# Schematic.net
KiCad netlist of a schematic drawn in Altium Designer
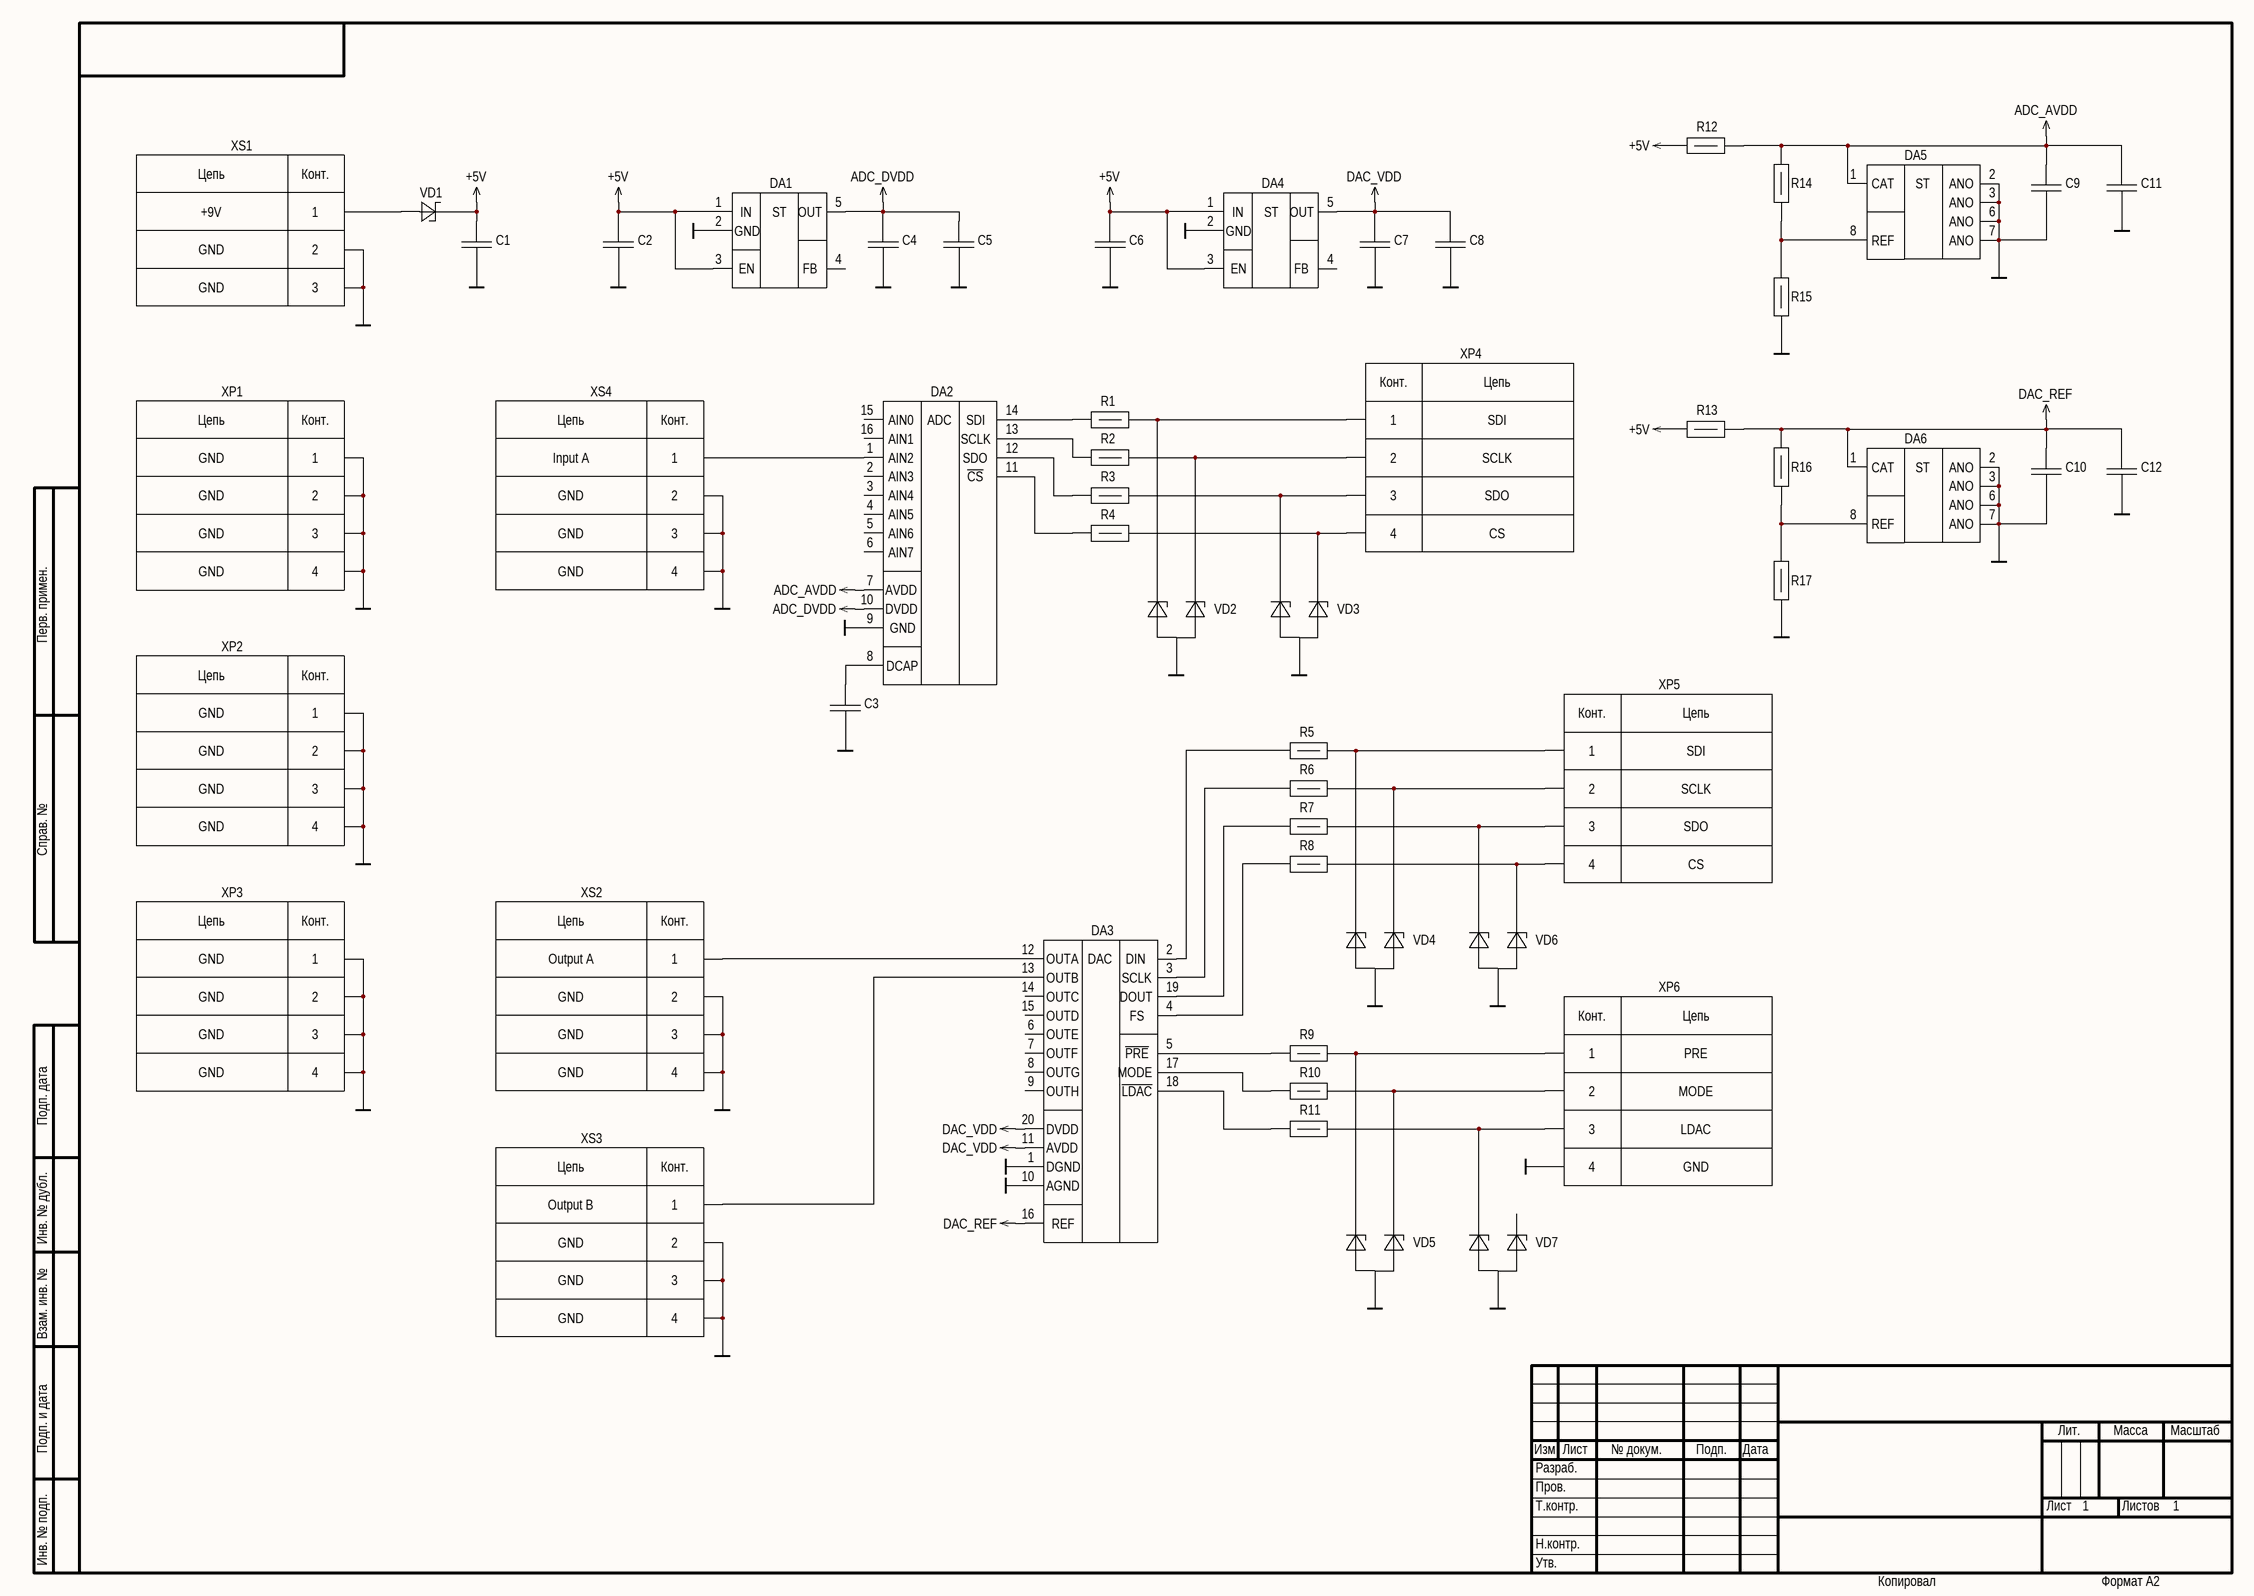
[diagram p0: Schematic.SchDoc]

(export (version "E")
  (design (tool "Eeschema 10.0.6"))
  (components
    (comp (ref "C1")
      (value "10 uF x 10 V")
      (footprint "CAPC2012X06N")
      (description "MLCC - Multilayer Ceramic Capacitors")
      (fields (field (name "TOLERANCE") "10%"))
      (libsource (lib "RLC") (part "KGM21AR71A106KU"))
    )
    (comp (ref "C2")
      (value "10 uF x 10 V")
      (footprint "CAPC2012X06N")
      (description "MLCC - Multilayer Ceramic Capacitors")
      (fields (field (name "TOLERANCE") "10%"))
      (libsource (lib "RLC") (part "KGM21AR71A106KU"))
    )
    (comp (ref "C3")
      (value "1 uF x 50 V")
      (footprint "CAPC2012X06N")
      (description "MLCC - Multilayer Ceramic Capacitors")
      (fields (field (name "TOLERANCE") "10%"))
      (libsource (lib "RLC") (part "KGF21KR71H105KU"))
    )
    (comp (ref "C4")
      (value "10 uF x 10 V")
      (footprint "CAPC2012X06N")
      (description "MLCC - Multilayer Ceramic Capacitors")
      (fields (field (name "TOLERANCE") "10%"))
      (libsource (lib "RLC") (part "KGM21AR71A106KU"))
    )
    (comp (ref "C5")
      (value "1 uF x 50 V")
      (footprint "CAPC2012X06N")
      (description "MLCC - Multilayer Ceramic Capacitors")
      (fields (field (name "TOLERANCE") "10%"))
      (libsource (lib "RLC") (part "KGF21KR71H105KU"))
    )
    (comp (ref "C6")
      (value "10 uF x 10 V")
      (footprint "CAPC2012X06N")
      (description "MLCC - Multilayer Ceramic Capacitors")
      (fields (field (name "TOLERANCE") "10%"))
      (libsource (lib "RLC") (part "KGM21AR71A106KU"))
    )
    (comp (ref "C7")
      (value "10 uF x 10 V")
      (footprint "CAPC2012X06N")
      (description "MLCC - Multilayer Ceramic Capacitors")
      (fields (field (name "TOLERANCE") "10%"))
      (libsource (lib "RLC") (part "KGM21AR71A106KU"))
    )
    (comp (ref "C8")
      (value "1 uF x 50 V")
      (footprint "CAPC2012X06N")
      (description "MLCC - Multilayer Ceramic Capacitors")
      (fields (field (name "TOLERANCE") "10%"))
      (libsource (lib "RLC") (part "KGF21KR71H105KU"))
    )
    (comp (ref "C9")
      (value "1 uF x 50 V")
      (footprint "CAPC2012X06N")
      (description "MLCC - Multilayer Ceramic Capacitors")
      (fields (field (name "TOLERANCE") "10%"))
      (libsource (lib "RLC") (part "KGF21KR71H105KU"))
    )
    (comp (ref "C10")
      (value "1 uF x 50 V")
      (footprint "CAPC2012X06N")
      (description "MLCC - Multilayer Ceramic Capacitors")
      (fields (field (name "TOLERANCE") "10%"))
      (libsource (lib "RLC") (part "KGF21KR71H105KU"))
    )
    (comp (ref "C11")
      (value "10 uF x 10 V")
      (footprint "CAPC2012X06N")
      (description "MLCC - Multilayer Ceramic Capacitors")
      (fields (field (name "TOLERANCE") "10%"))
      (libsource (lib "RLC") (part "KGM21AR71A106KU"))
    )
    (comp (ref "C12")
      (value "10 uF x 10 V")
      (footprint "CAPC2012X06N")
      (description "MLCC - Multilayer Ceramic Capacitors")
      (fields (field (name "TOLERANCE") "10%"))
      (libsource (lib "RLC") (part "KGM21AR71A106KU"))
    )
    (comp (ref "DA1")
      (value "TPS76333DBVT")
      (footprint "DBV0005A")
      (description "150mA, 10V, Low-Dropout Voltage Regulator")
      (libsource (lib "TPS763") (part "TPS76333DBVT"))
    )
    (comp (ref "DA2")
      (value "ADS7038IRTET")
      (footprint "RTE0016C")
      (description "Small, 8-Channel, 12-Bit ADC With SPI Interface, GPIOs, and CRC")
      (libsource (lib "ADS7038x") (part "ADS7038IRTET"))
    )
    (comp (ref "DA3")
      (value "TLV5631IPW")
      (footprint "PW0020A")
      (libsource (lib "TLV563x") (part "TLV5631IPW"))
    )
    (comp (ref "DA4")
      (value "TPS76333DBVT")
      (footprint "DBV0005A")
      (description "150mA, 10V, Low-Dropout Voltage Regulator")
      (libsource (lib "TPS763") (part "TPS76333DBVT"))
    )
    (comp (ref "DA5") (value "TL431AID") (footprint "D0008A") (libsource (lib "TL431") (part "TL431AID")))
    (comp (ref "DA6") (value "TL431AID") (footprint "D0008A") (libsource (lib "TL431") (part "TL431AID")))
    (comp (ref "R1")
      (value "22 Ohms")
      (footprint "RESC2012X06N")
      (description "Thick Film Chip Resistors")
      (fields (field (name "TOLERANCE") "1%"))
      (libsource (lib "RLC") (part "RCA080522R0FKEA"))
    )
    (comp (ref "R2")
      (value "22 Ohms")
      (footprint "RESC2012X06N")
      (description "Thick Film Chip Resistors")
      (fields (field (name "TOLERANCE") "1%"))
      (libsource (lib "RLC") (part "RCA080522R0FKEA"))
    )
    (comp (ref "R3")
      (value "22 Ohms")
      (footprint "RESC2012X06N")
      (description "Thick Film Chip Resistors")
      (fields (field (name "TOLERANCE") "1%"))
      (libsource (lib "RLC") (part "RCA080522R0FKEA"))
    )
    (comp (ref "R4")
      (value "22 Ohms")
      (footprint "RESC2012X06N")
      (description "Thick Film Chip Resistors")
      (fields (field (name "TOLERANCE") "1%"))
      (libsource (lib "RLC") (part "RCA080522R0FKEA"))
    )
    (comp (ref "R5")
      (value "22 Ohms")
      (footprint "RESC2012X06N")
      (description "Thick Film Chip Resistors")
      (fields (field (name "TOLERANCE") "1%"))
      (libsource (lib "RLC") (part "RCA080522R0FKEA"))
    )
    (comp (ref "R6")
      (value "22 Ohms")
      (footprint "RESC2012X06N")
      (description "Thick Film Chip Resistors")
      (fields (field (name "TOLERANCE") "1%"))
      (libsource (lib "RLC") (part "RCA080522R0FKEA"))
    )
    (comp (ref "R7")
      (value "22 Ohms")
      (footprint "RESC2012X06N")
      (description "Thick Film Chip Resistors")
      (fields (field (name "TOLERANCE") "1%"))
      (libsource (lib "RLC") (part "RCA080522R0FKEA"))
    )
    (comp (ref "R8")
      (value "22 Ohms")
      (footprint "RESC2012X06N")
      (description "Thick Film Chip Resistors")
      (fields (field (name "TOLERANCE") "1%"))
      (libsource (lib "RLC") (part "RCA080522R0FKEA"))
    )
    (comp (ref "R9")
      (value "22 Ohms")
      (footprint "RESC2012X06N")
      (description "Thick Film Chip Resistors")
      (fields (field (name "TOLERANCE") "1%"))
      (libsource (lib "RLC") (part "RCA080522R0FKEA"))
    )
    (comp (ref "R10")
      (value "22 Ohms")
      (footprint "RESC2012X06N")
      (description "Thick Film Chip Resistors")
      (fields (field (name "TOLERANCE") "1%"))
      (libsource (lib "RLC") (part "RCA080522R0FKEA"))
    )
    (comp (ref "R11")
      (value "22 Ohms")
      (footprint "RESC2012X06N")
      (description "Thick Film Chip Resistors")
      (fields (field (name "TOLERANCE") "1%"))
      (libsource (lib "RLC") (part "RCA080522R0FKEA"))
    )
    (comp (ref "R12")
      (value "182 Ohms")
      (footprint "RESC2012X06N")
      (description "Thick Film Chip Resistors")
      (fields (field (name "TOLERANCE") "1%"))
      (libsource (lib "RLC") (part "CR0805-FX-1820ELF"))
    )
    (comp (ref "R13")
      (value "182 Ohms")
      (footprint "RESC2012X06N")
      (description "Thick Film Chip Resistors")
      (fields (field (name "TOLERANCE") "1%"))
      (libsource (lib "RLC") (part "CR0805-FX-1820ELF"))
    )
    (comp (ref "R14")
      (value "3.3 kOhms")
      (footprint "RESC2012X06N")
      (description "Thick Film Chip Resistors")
      (fields (field (name "TOLERANCE") "1%"))
      (libsource (lib "RLC") (part "CR0805-FX-3301ELF"))
    )
    (comp (ref "R15")
      (value "10 kOhms")
      (footprint "RESC2012X06N")
      (description "Thick Film Chip Resistors")
      (fields (field (name "TOLERANCE") "1%"))
      (libsource (lib "RLC") (part "ERJ-6ENF1002V"))
    )
    (comp (ref "R16")
      (value "3.3 kOhms")
      (footprint "RESC2012X06N")
      (description "Thick Film Chip Resistors")
      (fields (field (name "TOLERANCE") "1%"))
      (libsource (lib "RLC") (part "CR0805-FX-3301ELF"))
    )
    (comp (ref "R17")
      (value "10 kOhms")
      (footprint "RESC2012X06N")
      (description "Thick Film Chip Resistors")
      (fields (field (name "TOLERANCE") "1%"))
      (libsource (lib "RLC") (part "ERJ-6ENF1002V"))
    )
    (comp (ref "VD1")
      (value "BAT54W-HG3-18")
      (footprint "SOD-123")
      (description "Schottky Diodes & Rectifiers 30V Schottky DIODE")
      (libsource (lib "BAT54W-HG3-18") (part "BAT54W-HG3-18"))
    )
    (comp (ref "VD2")
      (value "SP0502BAHT")
      (footprint "SOT23")
      (description "TVS Diode Array")
      (libsource (lib "SP05xxBA") (part "SP0502BAHT"))
    )
    (comp (ref "VD3")
      (value "SP0502BAHT")
      (footprint "SOT23")
      (description "TVS Diode Array")
      (libsource (lib "SP05xxBA") (part "SP0502BAHT"))
    )
    (comp (ref "VD4")
      (value "SP0502BAHT")
      (footprint "SOT23")
      (description "TVS Diode Array")
      (libsource (lib "SP05xxBA") (part "SP0502BAHT"))
    )
    (comp (ref "VD5")
      (value "SP0502BAHT")
      (footprint "SOT23")
      (description "TVS Diode Array")
      (libsource (lib "SP05xxBA") (part "SP0502BAHT"))
    )
    (comp (ref "VD6")
      (value "SP0502BAHT")
      (footprint "SOT23")
      (description "TVS Diode Array")
      (libsource (lib "SP05xxBA") (part "SP0502BAHT"))
    )
    (comp (ref "VD7")
      (value "SP0502BAHT")
      (footprint "SOT23")
      (description "TVS Diode Array")
      (libsource (lib "SP05xxBA") (part "SP0502BAHT"))
    )
    (comp (ref "XP1")
      (value "M20-9770346-4")
      (footprint "HDRV4W64P254_1X4_1016X254X834P")
      (description "Header 2.54mm")
      (libsource (lib "") (part "M20-9770346-4_1"))
    )
    (comp (ref "XP2")
      (value "M20-9770346-4")
      (footprint "HDRV4W64P254_1X4_1016X254X834P")
      (description "Header 2.54mm")
      (libsource (lib "") (part "M20-9770346-4_1"))
    )
    (comp (ref "XP3")
      (value "M20-9770346-4")
      (footprint "HDRV4W64P254_1X4_1016X254X834P")
      (description "Header 2.54mm")
      (libsource (lib "") (part "M20-9770346-4_1"))
    )
    (comp (ref "XP4")
      (value "M20-9770346-4")
      (footprint "HDRV4W64P254_1X4_1016X254X834P")
      (description "Header 2.54mm")
      (libsource (lib "M20-9770346-4") (part "M20-9770346-4"))
    )
    (comp (ref "XP5")
      (value "M20-9770346-4")
      (footprint "HDRV4W64P254_1X4_1016X254X834P")
      (description "Header 2.54mm")
      (libsource (lib "M20-9770346-4") (part "M20-9770346-4"))
    )
    (comp (ref "XP6")
      (value "M20-9770346-4")
      (footprint "HDRV4W64P254_1X4_1016X254X834P")
      (description "Header 2.54mm")
      (libsource (lib "") (part "M20-9770346-4_2"))
    )
    (comp (ref "XS1")
      (value "PJ-002AH")
      (footprint "PJ-002AH (Same Sky)")
      (description "DC POWER JACK")
      (libsource (lib "PJ-002AH") (part "PJ-002AH"))
    )
    (comp (ref "XS2")
      (value "0731385003")
      (footprint "0731385003 (Molex)")
      (description "BNC Connector Jack")
      (libsource (lib "") (part "0731385003_2"))
    )
    (comp (ref "XS3")
      (value "0731385003")
      (footprint "0731385003 (Molex)")
      (description "BNC Connector Jack")
      (libsource (lib "0731385003") (part "0731385003"))
    )
    (comp (ref "XS4")
      (value "0731385003")
      (footprint "0731385003 (Molex)")
      (description "BNC Connector Jack")
      (libsource (lib "") (part "0731385003_1"))
    )
  )
  (nets
    (net (code "1") (name "+5V") (class "Default")
      (node (ref "C1") (pin "1") (pinfunction "1_1") (pintype "passive"))
      (node (ref "C2") (pin "1") (pinfunction "1_1") (pintype "passive"))
      (node (ref "C6") (pin "1") (pinfunction "1_1") (pintype "passive"))
      (node (ref "DA1") (pin "1") (pinfunction "IN_1") (pintype "passive"))
      (node (ref "DA1") (pin "3") (pinfunction "EN_3") (pintype "passive"))
      (node (ref "DA4") (pin "1") (pinfunction "IN_1") (pintype "passive"))
      (node (ref "DA4") (pin "3") (pinfunction "EN_3") (pintype "passive"))
      (node (ref "R12") (pin "1") (pinfunction "1_1") (pintype "passive"))
      (node (ref "R13") (pin "1") (pinfunction "1_1") (pintype "passive"))
      (node (ref "VD1") (pin "1") (pinfunction "1_1") (pintype "passive"))
    )
    (net (code "2") (name "ADC_AVDD") (class "Default")
      (node (ref "C11") (pin "1") (pinfunction "1_1") (pintype "passive"))
      (node (ref "C9") (pin "1") (pinfunction "1_1") (pintype "passive"))
      (node (ref "DA2") (pin "7") (pinfunction "AVDD_7") (pintype "passive"))
      (node (ref "DA5") (pin "1") (pinfunction "CAT_1") (pintype "passive"))
      (node (ref "R12") (pin "2") (pinfunction "2_2") (pintype "passive"))
      (node (ref "R14") (pin "2") (pinfunction "2_2") (pintype "passive"))
    )
    (net (code "3") (name "ADC_DVDD") (class "Default")
      (node (ref "C4") (pin "1") (pinfunction "1_1") (pintype "passive"))
      (node (ref "C5") (pin "1") (pinfunction "1_1") (pintype "passive"))
      (node (ref "DA1") (pin "5") (pinfunction "OUT_5") (pintype "passive"))
      (node (ref "DA2") (pin "10") (pinfunction "DVDD_10") (pintype "passive"))
    )
    (net (code "4") (name "DAC_REF") (class "Default")
      (node (ref "C10") (pin "1") (pinfunction "1_1") (pintype "passive"))
      (node (ref "C12") (pin "1") (pinfunction "1_1") (pintype "passive"))
      (node (ref "DA3") (pin "16") (pinfunction "REF_16") (pintype "passive"))
      (node (ref "DA6") (pin "1") (pinfunction "CAT_1") (pintype "passive"))
      (node (ref "R13") (pin "2") (pinfunction "2_2") (pintype "passive"))
      (node (ref "R16") (pin "2") (pinfunction "2_2") (pintype "passive"))
    )
    (net (code "5") (name "DAC_VDD") (class "Default")
      (node (ref "C7") (pin "1") (pinfunction "1_1") (pintype "passive"))
      (node (ref "C8") (pin "1") (pinfunction "1_1") (pintype "passive"))
      (node (ref "DA3") (pin "11") (pinfunction "AVDD_11") (pintype "passive"))
      (node (ref "DA3") (pin "20") (pinfunction "DVDD_20") (pintype "passive"))
      (node (ref "DA4") (pin "5") (pinfunction "OUT_5") (pintype "passive"))
    )
    (net (code "6") (name "GND") (class "Default")
      (node (ref "C1") (pin "2") (pinfunction "2_2") (pintype "passive"))
      (node (ref "C10") (pin "2") (pinfunction "2_2") (pintype "passive"))
      (node (ref "C11") (pin "2") (pinfunction "2_2") (pintype "passive"))
      (node (ref "C12") (pin "2") (pinfunction "2_2") (pintype "passive"))
      (node (ref "C2") (pin "2") (pinfunction "2_2") (pintype "passive"))
      (node (ref "C3") (pin "2") (pinfunction "2_2") (pintype "passive"))
      (node (ref "C4") (pin "2") (pinfunction "2_2") (pintype "passive"))
      (node (ref "C5") (pin "2") (pinfunction "2_2") (pintype "passive"))
      (node (ref "C6") (pin "2") (pinfunction "2_2") (pintype "passive"))
      (node (ref "C7") (pin "2") (pinfunction "2_2") (pintype "passive"))
      (node (ref "C8") (pin "2") (pinfunction "2_2") (pintype "passive"))
      (node (ref "C9") (pin "2") (pinfunction "2_2") (pintype "passive"))
      (node (ref "DA1") (pin "2") (pinfunction "GND_2") (pintype "passive"))
      (node (ref "DA2") (pin "9") (pinfunction "GND_9") (pintype "passive"))
      (node (ref "DA3") (pin "1") (pinfunction "DGND_1") (pintype "passive"))
      (node (ref "DA3") (pin "10") (pinfunction "AGND_10") (pintype "passive"))
      (node (ref "DA4") (pin "2") (pinfunction "GND_2") (pintype "passive"))
      (node (ref "DA5") (pin "2") (pinfunction "ANO_2") (pintype "passive"))
      (node (ref "DA5") (pin "3") (pinfunction "ANO_3") (pintype "passive"))
      (node (ref "DA5") (pin "6") (pinfunction "ANO_6") (pintype "passive"))
      (node (ref "DA5") (pin "7") (pinfunction "ANO_7") (pintype "passive"))
      (node (ref "DA6") (pin "2") (pinfunction "ANO_2") (pintype "passive"))
      (node (ref "DA6") (pin "3") (pinfunction "ANO_3") (pintype "passive"))
      (node (ref "DA6") (pin "6") (pinfunction "ANO_6") (pintype "passive"))
      (node (ref "DA6") (pin "7") (pinfunction "ANO_7") (pintype "passive"))
      (node (ref "R15") (pin "1") (pinfunction "1_1") (pintype "passive"))
      (node (ref "R17") (pin "1") (pinfunction "1_1") (pintype "passive"))
      (node (ref "VD2") (pin "3") (pinfunction "3_3") (pintype "passive"))
      (node (ref "VD3") (pin "3") (pinfunction "3_3") (pintype "passive"))
      (node (ref "VD4") (pin "3") (pinfunction "3_3") (pintype "passive"))
      (node (ref "VD5") (pin "3") (pinfunction "3_3") (pintype "passive"))
      (node (ref "VD6") (pin "3") (pinfunction "3_3") (pintype "passive"))
      (node (ref "VD7") (pin "3") (pinfunction "3_3") (pintype "passive"))
      (node (ref "XP1") (pin "1") (pinfunction "GND_1") (pintype "passive"))
      (node (ref "XP1") (pin "2") (pinfunction "GND_2") (pintype "passive"))
      (node (ref "XP1") (pin "3") (pinfunction "GND_3") (pintype "passive"))
      (node (ref "XP1") (pin "4") (pinfunction "GND_4") (pintype "passive"))
      (node (ref "XP2") (pin "1") (pinfunction "GND_1") (pintype "passive"))
      (node (ref "XP2") (pin "2") (pinfunction "GND_2") (pintype "passive"))
      (node (ref "XP2") (pin "3") (pinfunction "GND_3") (pintype "passive"))
      (node (ref "XP2") (pin "4") (pinfunction "GND_4") (pintype "passive"))
      (node (ref "XP3") (pin "1") (pinfunction "GND_1") (pintype "passive"))
      (node (ref "XP3") (pin "2") (pinfunction "GND_2") (pintype "passive"))
      (node (ref "XP3") (pin "3") (pinfunction "GND_3") (pintype "passive"))
      (node (ref "XP3") (pin "4") (pinfunction "GND_4") (pintype "passive"))
      (node (ref "XP6") (pin "4") (pinfunction "GND_4") (pintype "passive"))
      (node (ref "XS1") (pin "2") (pinfunction "GND_2") (pintype "passive"))
      (node (ref "XS1") (pin "3") (pinfunction "GND_3") (pintype "passive"))
      (node (ref "XS2") (pin "2") (pinfunction "GND_2") (pintype "passive"))
      (node (ref "XS2") (pin "3") (pinfunction "GND_3") (pintype "passive"))
      (node (ref "XS2") (pin "4") (pinfunction "GND_4") (pintype "passive"))
      (node (ref "XS3") (pin "2") (pinfunction "GND_2") (pintype "passive"))
      (node (ref "XS3") (pin "3") (pinfunction "GND_3") (pintype "passive"))
      (node (ref "XS3") (pin "4") (pinfunction "GND_4") (pintype "passive"))
      (node (ref "XS4") (pin "2") (pinfunction "GND_2") (pintype "passive"))
      (node (ref "XS4") (pin "3") (pinfunction "GND_3") (pintype "passive"))
      (node (ref "XS4") (pin "4") (pinfunction "GND_4") (pintype "passive"))
    )
    (net (code "7") (name "Net-(DA2-AIN2)") (class "Default")
      (node (ref "DA2") (pin "1") (pinfunction "AIN2_1") (pintype "passive"))
      (node (ref "XS4") (pin "1") (pinfunction "Input_A_1") (pintype "passive"))
    )
    (net (code "8") (name "Net-(DA2-CS)") (class "Default")
      (node (ref "DA2") (pin "11") (pinfunction "CS_11") (pintype "passive"))
      (node (ref "R4") (pin "1") (pinfunction "1_1") (pintype "passive"))
    )
    (net (code "9") (name "Net-(DA2-DCAP)") (class "Default")
      (node (ref "C3") (pin "1") (pinfunction "1_1") (pintype "passive"))
      (node (ref "DA2") (pin "8") (pinfunction "DCAP_8") (pintype "passive"))
    )
    (net (code "10") (name "Net-(DA2-SCLK)") (class "Default")
      (node (ref "DA2") (pin "13") (pinfunction "SCLK_13") (pintype "passive"))
      (node (ref "R2") (pin "1") (pinfunction "1_1") (pintype "passive"))
    )
    (net (code "11") (name "Net-(DA2-SDI)") (class "Default")
      (node (ref "DA2") (pin "14") (pinfunction "SDI_14") (pintype "passive"))
      (node (ref "R1") (pin "1") (pinfunction "1_1") (pintype "passive"))
    )
    (net (code "12") (name "Net-(DA2-SDO)") (class "Default")
      (node (ref "DA2") (pin "12") (pinfunction "SDO_12") (pintype "passive"))
      (node (ref "R3") (pin "1") (pinfunction "1_1") (pintype "passive"))
    )
    (net (code "13") (name "Net-(DA3-DIN)") (class "Default")
      (node (ref "DA3") (pin "2") (pinfunction "DIN_2") (pintype "passive"))
      (node (ref "R5") (pin "1") (pinfunction "1_1") (pintype "passive"))
    )
    (net (code "14") (name "Net-(DA3-DOUT)") (class "Default")
      (node (ref "DA3") (pin "19") (pinfunction "DOUT_19") (pintype "passive"))
      (node (ref "R7") (pin "1") (pinfunction "1_1") (pintype "passive"))
    )
    (net (code "15") (name "Net-(DA3-FS)") (class "Default")
      (node (ref "DA3") (pin "4") (pinfunction "FS_4") (pintype "passive"))
      (node (ref "R8") (pin "1") (pinfunction "1_1") (pintype "passive"))
    )
    (net (code "16") (name "Net-(DA3-LDAC)") (class "Default")
      (node (ref "DA3") (pin "18") (pinfunction "LDAC_18") (pintype "passive"))
      (node (ref "R11") (pin "1") (pinfunction "1_1") (pintype "passive"))
    )
    (net (code "17") (name "Net-(DA3-MODE)") (class "Default")
      (node (ref "DA3") (pin "17") (pinfunction "MODE_17") (pintype "passive"))
      (node (ref "R10") (pin "1") (pinfunction "1_1") (pintype "passive"))
    )
    (net (code "18") (name "Net-(DA3-OUTA)") (class "Default")
      (node (ref "DA3") (pin "12") (pinfunction "OUTA_12") (pintype "passive"))
      (node (ref "XS2") (pin "1") (pinfunction "Output_A_1") (pintype "passive"))
    )
    (net (code "19") (name "Net-(DA3-OUTB)") (class "Default")
      (node (ref "DA3") (pin "13") (pinfunction "OUTB_13") (pintype "passive"))
      (node (ref "XS3") (pin "1") (pinfunction "Output_B_1") (pintype "passive"))
    )
    (net (code "20") (name "Net-(DA3-PRE)") (class "Default")
      (node (ref "DA3") (pin "5") (pinfunction "PRE_5") (pintype "passive"))
      (node (ref "R9") (pin "1") (pinfunction "1_1") (pintype "passive"))
    )
    (net (code "21") (name "Net-(DA3-SCLK)") (class "Default")
      (node (ref "DA3") (pin "3") (pinfunction "SCLK_3") (pintype "passive"))
      (node (ref "R6") (pin "1") (pinfunction "1_1") (pintype "passive"))
    )
    (net (code "22") (name "Net-(DA5-REF)") (class "Default")
      (node (ref "DA5") (pin "8") (pinfunction "REF_8") (pintype "passive"))
      (node (ref "R14") (pin "1") (pinfunction "1_1") (pintype "passive"))
      (node (ref "R15") (pin "2") (pinfunction "2_2") (pintype "passive"))
    )
    (net (code "23") (name "Net-(DA6-REF)") (class "Default")
      (node (ref "DA6") (pin "8") (pinfunction "REF_8") (pintype "passive"))
      (node (ref "R16") (pin "1") (pinfunction "1_1") (pintype "passive"))
      (node (ref "R17") (pin "2") (pinfunction "2_2") (pintype "passive"))
    )
    (net (code "24") (name "Net-(XP4-CS)") (class "Default")
      (node (ref "R4") (pin "2") (pinfunction "2_2") (pintype "passive"))
      (node (ref "VD3") (pin "1") (pinfunction "1_1") (pintype "passive"))
      (node (ref "XP4") (pin "4") (pinfunction "CS_4") (pintype "passive"))
    )
    (net (code "25") (name "Net-(XP4-SCLK)") (class "Default")
      (node (ref "R2") (pin "2") (pinfunction "2_2") (pintype "passive"))
      (node (ref "VD2") (pin "1") (pinfunction "1_1") (pintype "passive"))
      (node (ref "XP4") (pin "2") (pinfunction "SCLK_2") (pintype "passive"))
    )
    (net (code "26") (name "Net-(XP4-SDI)") (class "Default")
      (node (ref "R1") (pin "2") (pinfunction "2_2") (pintype "passive"))
      (node (ref "VD2") (pin "2") (pinfunction "2_2") (pintype "passive"))
      (node (ref "XP4") (pin "1") (pinfunction "SDI_1") (pintype "passive"))
    )
    (net (code "27") (name "Net-(XP4-SDO)") (class "Default")
      (node (ref "R3") (pin "2") (pinfunction "2_2") (pintype "passive"))
      (node (ref "VD3") (pin "2") (pinfunction "2_2") (pintype "passive"))
      (node (ref "XP4") (pin "3") (pinfunction "SDO_3") (pintype "passive"))
    )
    (net (code "28") (name "Net-(XP5-CS)") (class "Default")
      (node (ref "R8") (pin "2") (pinfunction "2_2") (pintype "passive"))
      (node (ref "VD6") (pin "1") (pinfunction "1_1") (pintype "passive"))
      (node (ref "XP5") (pin "4") (pinfunction "CS_4") (pintype "passive"))
    )
    (net (code "29") (name "Net-(XP5-SCLK)") (class "Default")
      (node (ref "R6") (pin "2") (pinfunction "2_2") (pintype "passive"))
      (node (ref "VD4") (pin "1") (pinfunction "1_1") (pintype "passive"))
      (node (ref "XP5") (pin "2") (pinfunction "SCLK_2") (pintype "passive"))
    )
    (net (code "30") (name "Net-(XP5-SDI)") (class "Default")
      (node (ref "R5") (pin "2") (pinfunction "2_2") (pintype "passive"))
      (node (ref "VD4") (pin "2") (pinfunction "2_2") (pintype "passive"))
      (node (ref "XP5") (pin "1") (pinfunction "SDI_1") (pintype "passive"))
    )
    (net (code "31") (name "Net-(XP5-SDO)") (class "Default")
      (node (ref "R7") (pin "2") (pinfunction "2_2") (pintype "passive"))
      (node (ref "VD6") (pin "2") (pinfunction "2_2") (pintype "passive"))
      (node (ref "XP5") (pin "3") (pinfunction "SDO_3") (pintype "passive"))
    )
    (net (code "32") (name "Net-(XP6-LDAC)") (class "Default")
      (node (ref "R11") (pin "2") (pinfunction "2_2") (pintype "passive"))
      (node (ref "VD7") (pin "2") (pinfunction "2_2") (pintype "passive"))
      (node (ref "XP6") (pin "3") (pinfunction "LDAC_3") (pintype "passive"))
    )
    (net (code "33") (name "Net-(XP6-MODE)") (class "Default")
      (node (ref "R10") (pin "2") (pinfunction "2_2") (pintype "passive"))
      (node (ref "VD5") (pin "1") (pinfunction "1_1") (pintype "passive"))
      (node (ref "XP6") (pin "2") (pinfunction "MODE_2") (pintype "passive"))
    )
    (net (code "34") (name "Net-(XP6-PRE)") (class "Default")
      (node (ref "R9") (pin "2") (pinfunction "2_2") (pintype "passive"))
      (node (ref "VD5") (pin "2") (pinfunction "2_2") (pintype "passive"))
      (node (ref "XP6") (pin "1") (pinfunction "PRE_1") (pintype "passive"))
    )
    (net (code "35") (name "Net-(XS1-+9V)") (class "Default")
      (node (ref "VD1") (pin "2") (pinfunction "2_2") (pintype "passive"))
      (node (ref "XS1") (pin "1") (pinfunction "+9V_1") (pintype "passive"))
    )
    (net (code "36") (name "unconnected-(DA1-FB-Pad4)") (class "Default")
      (node (ref "DA1") (pin "4") (pinfunction "FB_4") (pintype "passive"))
    )
    (net (code "37") (name "unconnected-(DA2-AIN0-Pad15)") (class "Default")
      (node (ref "DA2") (pin "15") (pinfunction "AIN0_15") (pintype "passive"))
    )
    (net (code "38") (name "unconnected-(DA2-AIN1-Pad16)") (class "Default")
      (node (ref "DA2") (pin "16") (pinfunction "AIN1_16") (pintype "passive"))
    )
    (net (code "39") (name "unconnected-(DA2-AIN3-Pad2)") (class "Default")
      (node (ref "DA2") (pin "2") (pinfunction "AIN3_2") (pintype "passive"))
    )
    (net (code "40") (name "unconnected-(DA2-AIN4-Pad3)") (class "Default")
      (node (ref "DA2") (pin "3") (pinfunction "AIN4_3") (pintype "passive"))
    )
    (net (code "41") (name "unconnected-(DA2-AIN5-Pad4)") (class "Default")
      (node (ref "DA2") (pin "4") (pinfunction "AIN5_4") (pintype "passive"))
    )
    (net (code "42") (name "unconnected-(DA2-AIN6-Pad5)") (class "Default")
      (node (ref "DA2") (pin "5") (pinfunction "AIN6_5") (pintype "passive"))
    )
    (net (code "43") (name "unconnected-(DA2-AIN7-Pad6)") (class "Default")
      (node (ref "DA2") (pin "6") (pinfunction "AIN7_6") (pintype "passive"))
    )
    (net (code "44") (name "unconnected-(DA3-OUTC-Pad14)") (class "Default")
      (node (ref "DA3") (pin "14") (pinfunction "OUTC_14") (pintype "passive"))
    )
    (net (code "45") (name "unconnected-(DA3-OUTD-Pad15)") (class "Default")
      (node (ref "DA3") (pin "15") (pinfunction "OUTD_15") (pintype "passive"))
    )
    (net (code "46") (name "unconnected-(DA3-OUTE-Pad6)") (class "Default")
      (node (ref "DA3") (pin "6") (pinfunction "OUTE_6") (pintype "passive"))
    )
    (net (code "47") (name "unconnected-(DA3-OUTF-Pad7)") (class "Default")
      (node (ref "DA3") (pin "7") (pinfunction "OUTF_7") (pintype "passive"))
    )
    (net (code "48") (name "unconnected-(DA3-OUTG-Pad8)") (class "Default")
      (node (ref "DA3") (pin "8") (pinfunction "OUTG_8") (pintype "passive"))
    )
    (net (code "49") (name "unconnected-(DA3-OUTH-Pad9)") (class "Default")
      (node (ref "DA3") (pin "9") (pinfunction "OUTH_9") (pintype "passive"))
    )
    (net (code "50") (name "unconnected-(DA4-FB-Pad4)") (class "Default")
      (node (ref "DA4") (pin "4") (pinfunction "FB_4") (pintype "passive"))
    )
    (net (code "51") (name "unconnected-(VD7-Pad1)") (class "Default")
      (node (ref "VD7") (pin "1") (pinfunction "1_1") (pintype "passive"))
    )
  )
)
